# GTU-2-V1_0-20160324.net
KiCad netlist of a schematic drawn in Altium Designer
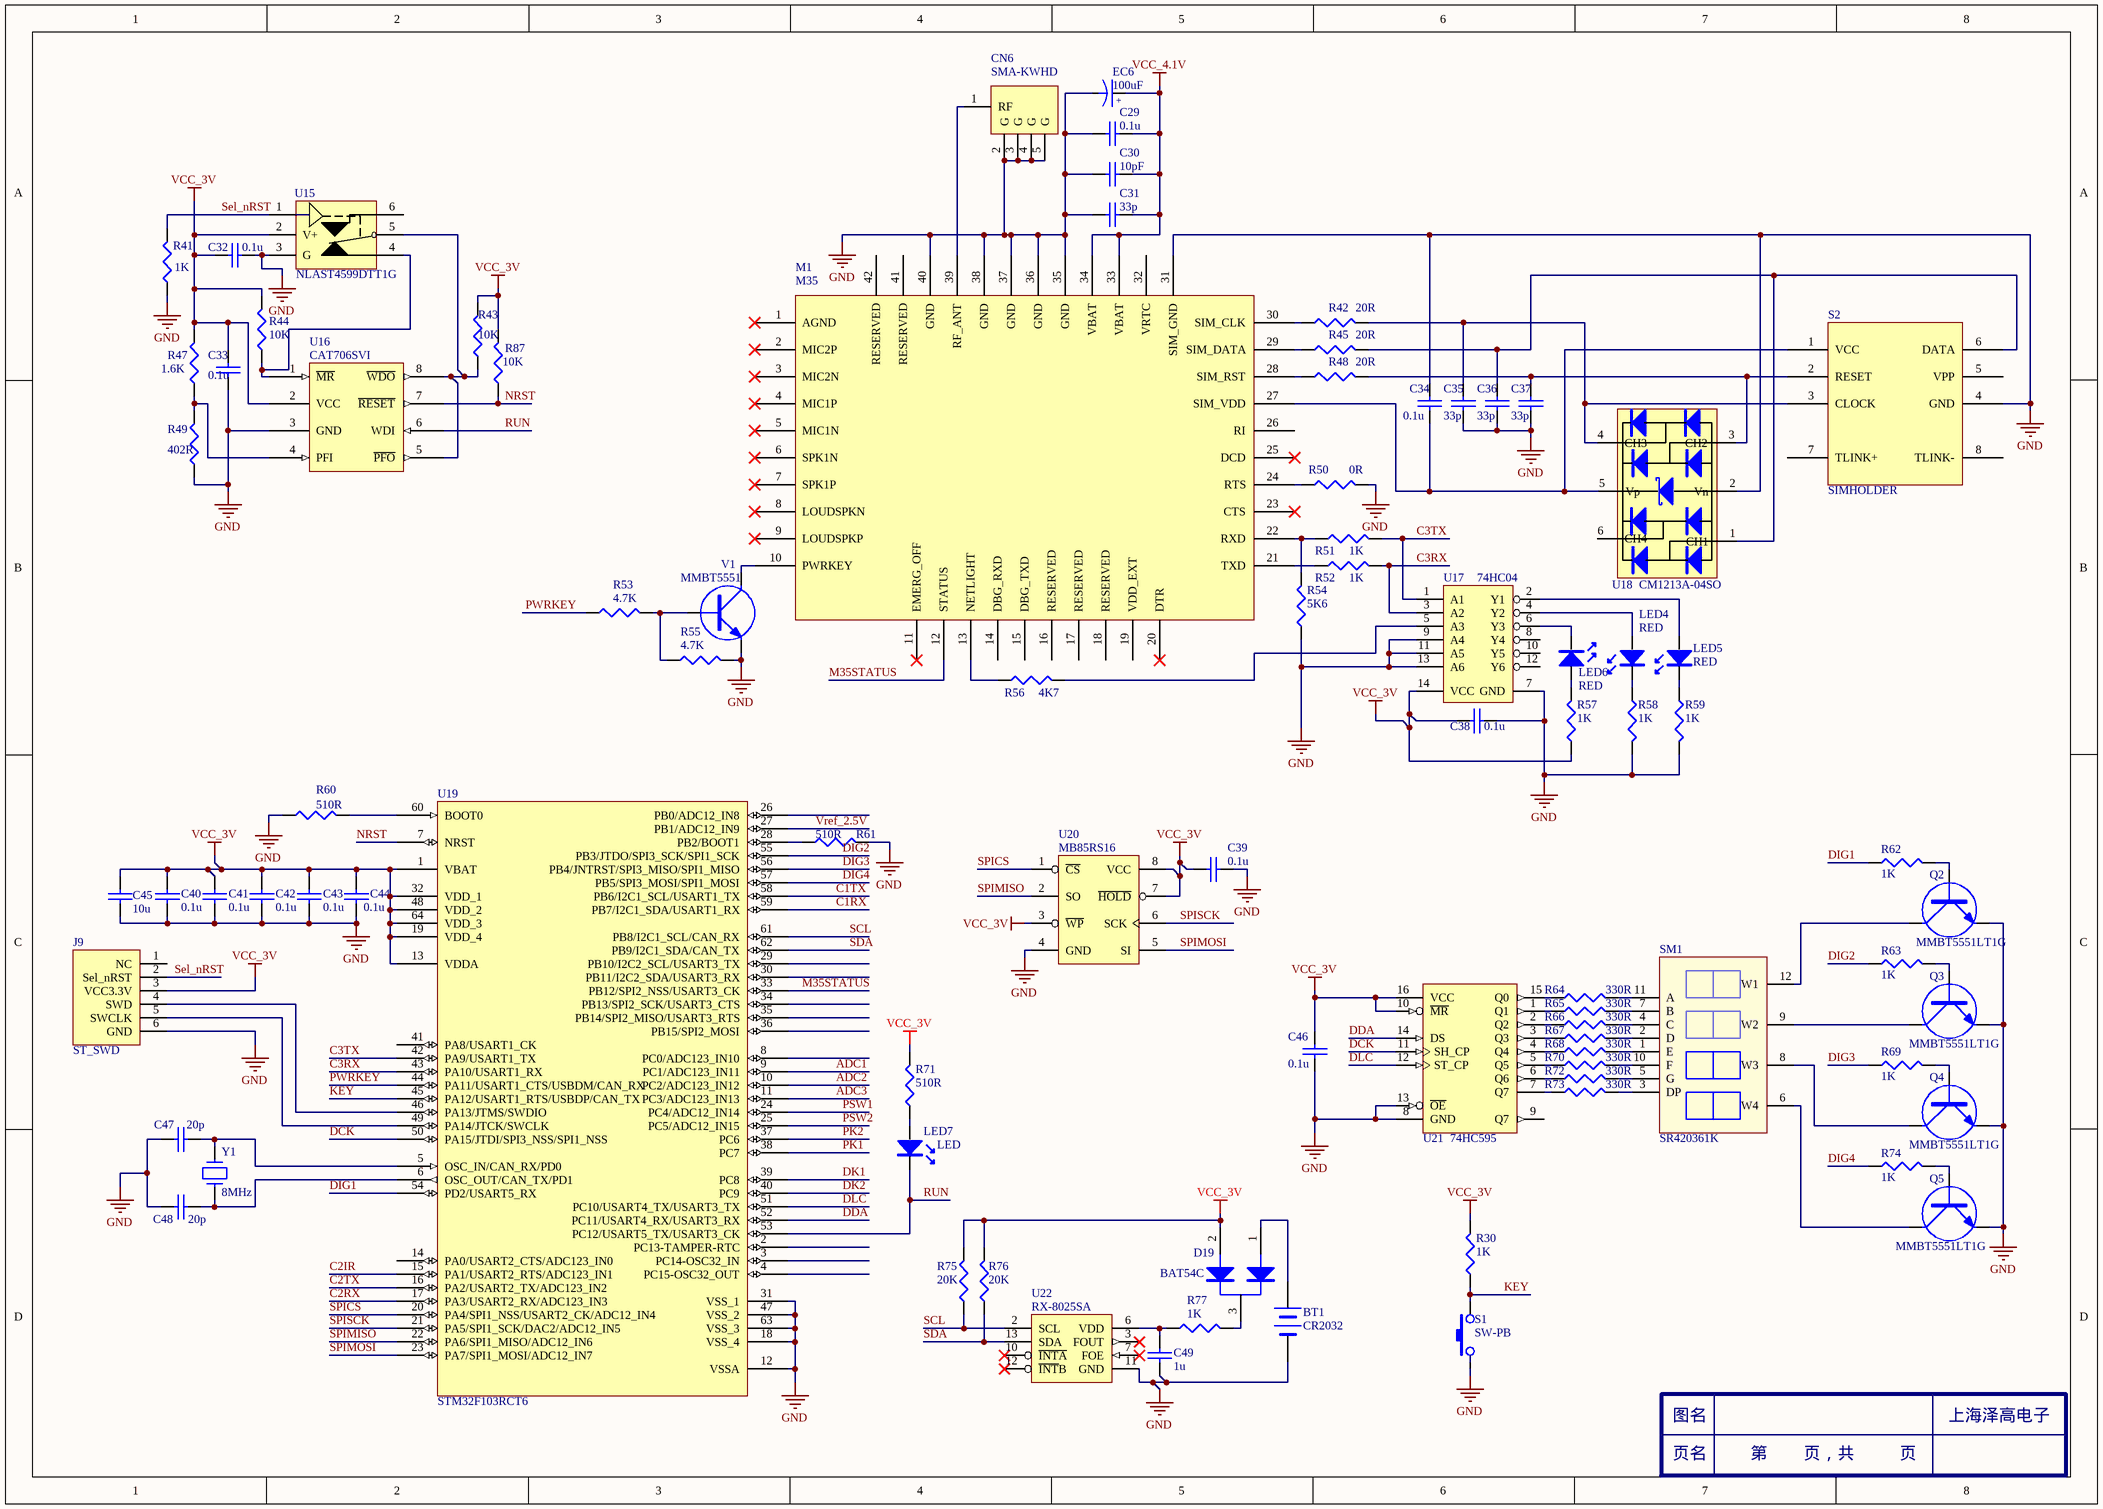
[diagram p0: GTU-2-V1.0-20160324.SCHDOC]

(export (version "E")
  (design (tool "Eeschema 10.0.6"))
  (components
    (comp (ref "4") (value "Component_1") (libsource (lib "*") (part "Component_1")))
    (comp (ref "BT1")
      (value "CR2032")
      (footprint "CR2032")
      (description "Battery")
      (libsource (lib "*") (part "BATTERY"))
    )
    (comp (ref "C29")
      (value "0.1u")
      (footprint "0805-C")
      (description "Capacitor")
      (libsource (lib "STSCH-2014-01-20    ") (part "CAP"))
    )
    (comp (ref "C30")
      (value "10pF")
      (footprint "0805-C")
      (description "Capacitor")
      (libsource (lib "STSCH-2014-01-20    ") (part "CAP"))
    )
    (comp (ref "C31")
      (value "33p")
      (footprint "0805-C")
      (description "Capacitor")
      (libsource (lib "STSCH-2014-01-20    ") (part "CAP"))
    )
    (comp (ref "C32")
      (value "0.1u")
      (footprint "0805-C")
      (description "Capacitor")
      (fields (field (name "MFG") "TDK"))
      (libsource (lib "SCHLIB-ZG-2015.12.11      ") (part "CAP"))
    )
    (comp (ref "C33")
      (value "0.1u")
      (footprint "0805-C")
      (description "Capacitor")
      (libsource (lib "STSCH-2011-12-16") (part "CAP"))
    )
    (comp (ref "C34")
      (value "0.1u")
      (footprint "0805-C")
      (description "Capacitor")
      (libsource (lib "STSCH-2014-01-20    ") (part "CAP"))
    )
    (comp (ref "C35")
      (value "33p")
      (footprint "0805-C")
      (description "Capacitor")
      (libsource (lib "STSCH-2014-01-20    ") (part "CAP"))
    )
    (comp (ref "C36")
      (value "33p")
      (footprint "0805-C")
      (description "Capacitor")
      (libsource (lib "STSCH-2014-01-20    ") (part "CAP"))
    )
    (comp (ref "C37")
      (value "33p")
      (footprint "0805-C")
      (description "Capacitor")
      (libsource (lib "STSCH-2014-01-20    ") (part "CAP"))
    )
    (comp (ref "C38")
      (value "0.1u")
      (footprint "0805-C")
      (description "Capacitor")
      (libsource (lib "STSCH-2013-02-22   ") (part "CAP"))
    )
    (comp (ref "C39")
      (value "0.1u")
      (footprint "0805-C")
      (description "Capacitor")
      (libsource (lib "STSCH-2013-02-22   ") (part "CAP"))
    )
    (comp (ref "C40")
      (value "0.1u")
      (footprint "0805-C")
      (description "Capacitor")
      (libsource (lib "*") (part "CAP"))
    )
    (comp (ref "C41")
      (value "0.1u")
      (footprint "0805-C")
      (description "Capacitor")
      (libsource (lib "*") (part "CAP"))
    )
    (comp (ref "C42")
      (value "0.1u")
      (footprint "0805-C")
      (description "Capacitor")
      (libsource (lib "*") (part "CAP"))
    )
    (comp (ref "C43")
      (value "0.1u")
      (footprint "0805-C")
      (description "Capacitor")
      (libsource (lib "*") (part "CAP"))
    )
    (comp (ref "C44")
      (value "0.1u")
      (footprint "0805-C")
      (description "Capacitor")
      (libsource (lib "*") (part "CAP"))
    )
    (comp (ref "C45")
      (value "10u")
      (footprint "0805-C")
      (description "Capacitor")
      (libsource (lib "*") (part "CAP"))
    )
    (comp (ref "C46")
      (value "0.1u")
      (footprint "0805-C")
      (description "Capacitor")
      (libsource (lib "STSCH-2013-02-22   ") (part "CAP"))
    )
    (comp (ref "C47")
      (value "20p")
      (footprint "0805-C")
      (description "Capacitor")
      (libsource (lib "*") (part "CAP"))
    )
    (comp (ref "C48")
      (value "20p")
      (footprint "0805-C")
      (description "Capacitor")
      (libsource (lib "*") (part "CAP"))
    )
    (comp (ref "C49")
      (value "1u")
      (footprint "0805-C")
      (description "Capacitor")
      (libsource (lib "") (part "CAP_1"))
    )
    (comp (ref "CN6")
      (value "SMA-KWHD")
      (footprint "SMA-KWHD")
      (description "RF插座")
      (libsource (lib "STSCH-2014-02-13    ") (part "SMA-KWHD"))
    )
    (comp (ref "D19") (value "BAT54C") (footprint "BAT54S/SOT-23") (libsource (lib "*") (part "BAT54C")))
    (comp (ref "EC6")
      (value "100uF")
      (footprint "7361-V")
      (libsource (lib "STSCH-2014-01-20    ") (part "CAP Tan"))
    )
    (comp (ref "J9")
      (value "ST_SWD")
      (footprint "SWD_DOWNLOAD")
      (description "STM32 SWD调试端口")
      (libsource (lib "SCHLIB-ZG-2015.12.11      ") (part "ST_SWD"))
    )
    (comp (ref "LED4")
      (value "RED")
      (footprint "0805-LED")
      (libsource (lib "STSCH-2012-11-26   ") (part "LED"))
    )
    (comp (ref "LED5")
      (value "RED")
      (footprint "0805-LED")
      (libsource (lib "STSCH-2012-11-26   ") (part "LED"))
    )
    (comp (ref "LED6")
      (value "RED")
      (footprint "0805-LED")
      (libsource (lib "STSCH-2012-11-26   ") (part "LED"))
    )
    (comp (ref "LED7") (value "LED") (footprint "0805-LED") (libsource (lib "STSCH-20110618") (part "LED")))
    (comp (ref "M1") (value "M35") (footprint "M35") (libsource (lib "STSCH-2014-01-20    ") (part "M35")))
    (comp (ref "Q2")
      (value "MMBT5551")
      (footprint "SOT-23")
      (description "NPN Transistor 160V 0.6A")
      (fields (field (name "MFG") "DIODES") (field (name "MFG2-PN") "MMBT5551LT1G"))
      (libsource (lib "SCHLIB-ZG-2016.01.18      ") (part "MMBT5551"))
    )
    (comp (ref "Q3")
      (value "MMBT5551")
      (footprint "SOT-23")
      (description "NPN Transistor 160V 0.6A")
      (fields (field (name "MFG") "DIODES") (field (name "MFG2-PN") "MMBT5551LT1G"))
      (libsource (lib "SCHLIB-ZG-2016.01.18      ") (part "MMBT5551"))
    )
    (comp (ref "Q4")
      (value "MMBT5551")
      (footprint "SOT-23")
      (description "NPN Transistor 160V 0.6A")
      (fields (field (name "MFG") "DIODES") (field (name "MFG2-PN") "MMBT5551LT1G"))
      (libsource (lib "SCHLIB-ZG-2016.01.18      ") (part "MMBT5551"))
    )
    (comp (ref "Q5")
      (value "MMBT5551")
      (footprint "SOT-23")
      (description "NPN Transistor 160V 0.6A")
      (fields (field (name "MFG") "DIODES") (field (name "MFG2-PN") "MMBT5551LT1G"))
      (libsource (lib "SCHLIB-ZG-2016.01.18      ") (part "MMBT5551"))
    )
    (comp (ref "R30") (value "1K") (footprint "0805-R") (libsource (lib "STSCH-2014-03-27    ") (part "RES")))
    (comp (ref "R41")
      (value "1K")
      (footprint "0805-R")
      (description "电阻")
      (fields (field (name "MFG") "YAGO") (field (name "Comment") "RES"))
      (libsource (lib "SCHLIB-ZG-2015.12.11      ") (part "RES"))
    )
    (comp (ref "R42")
      (value "20R")
      (footprint "0805-R")
      (libsource (lib "STSCH-2014-01-20    ") (part "RES"))
    )
    (comp (ref "R43") (value "10K") (footprint "0805-R") (libsource (lib "*") (part "RES")))
    (comp (ref "R44") (value "10K") (footprint "0805-R") (libsource (lib "*") (part "RES")))
    (comp (ref "R45")
      (value "20R")
      (footprint "0805-R")
      (libsource (lib "STSCH-2014-01-20    ") (part "RES"))
    )
    (comp (ref "R47")
      (value "1.6K")
      (footprint "0805-R")
      (description "电阻")
      (fields (field (name "MFG") "YAGO"))
      (libsource (lib "SCHLIB-ZG-2015.12.11      ") (part "RES"))
    )
    (comp (ref "R48")
      (value "20R")
      (footprint "0805-R")
      (libsource (lib "STSCH-2014-01-20    ") (part "RES"))
    )
    (comp (ref "R49")
      (value "402R")
      (footprint "0805-R")
      (description "电阻")
      (fields (field (name "MFG") "YAGO"))
      (libsource (lib "SCHLIB-ZG-2015.12.11      ") (part "RES"))
    )
    (comp (ref "R50") (value "0R") (footprint "0805-R") (libsource (lib "STSCH-2014-01-20    ") (part "RES")))
    (comp (ref "R51") (value "1K") (footprint "0805-R") (libsource (lib "STSCH-2014-01-20    ") (part "RES")))
    (comp (ref "R52") (value "1K") (footprint "0805-R") (libsource (lib "STSCH-2014-01-20    ") (part "RES")))
    (comp (ref "R53")
      (value "4.7K")
      (footprint "0805-R")
      (libsource (lib "STSCH-2014-01-20    ") (part "RES"))
    )
    (comp (ref "R54")
      (value "5K6")
      (footprint "0805-R")
      (libsource (lib "STSCH-2014-01-20    ") (part "RES"))
    )
    (comp (ref "R55")
      (value "4.7K")
      (footprint "0805-R")
      (libsource (lib "STSCH-2014-01-20    ") (part "RES"))
    )
    (comp (ref "R56")
      (value "4K7")
      (footprint "0805-R")
      (libsource (lib "STSCH-2014-02-12    ") (part "RES"))
    )
    (comp (ref "R57") (value "1K") (footprint "0805-R") (libsource (lib "STSCH-2012-11-26   ") (part "RES")))
    (comp (ref "R58") (value "1K") (footprint "0805-R") (libsource (lib "STSCH-2012-11-26   ") (part "RES")))
    (comp (ref "R59") (value "1K") (footprint "0805-R") (libsource (lib "STSCH-2012-11-26   ") (part "RES")))
    (comp (ref "R60") (value "510R") (footprint "0805-R") (libsource (lib "*") (part "RES")))
    (comp (ref "R61") (value "510R") (footprint "0805-R") (libsource (lib "*") (part "RES")))
    (comp (ref "R62")
      (value "1K")
      (footprint "0805-R")
      (description "电阻")
      (fields (field (name "MFG") "YAGO") (field (name "Comment") "RES"))
      (libsource (lib "SCHLIB-ZG-2016.01.18      ") (part "RES"))
    )
    (comp (ref "R63")
      (value "1K")
      (footprint "0805-R")
      (description "电阻")
      (fields (field (name "MFG") "YAGO") (field (name "Comment") "RES"))
      (libsource (lib "SCHLIB-ZG-2016.01.18      ") (part "RES"))
    )
    (comp (ref "R64") (value "330R") (footprint "0805-R") (libsource (lib "") (part "RES_1")))
    (comp (ref "R65") (value "330R") (footprint "0805-R") (libsource (lib "") (part "RES_1")))
    (comp (ref "R66") (value "330R") (footprint "0805-R") (libsource (lib "") (part "RES_1")))
    (comp (ref "R67") (value "330R") (footprint "0805-R") (libsource (lib "") (part "RES_1")))
    (comp (ref "R68") (value "330R") (footprint "0805-R") (libsource (lib "") (part "RES_1")))
    (comp (ref "R69")
      (value "1K")
      (footprint "0805-R")
      (description "电阻")
      (fields (field (name "MFG") "YAGO") (field (name "Comment") "RES"))
      (libsource (lib "SCHLIB-ZG-2016.01.18      ") (part "RES"))
    )
    (comp (ref "R70") (value "330R") (footprint "0805-R") (libsource (lib "") (part "RES_1")))
    (comp (ref "R71") (value "510R") (footprint "0805-R") (libsource (lib "STSCH-20110618") (part "RES")))
    (comp (ref "R72") (value "330R") (footprint "0805-R") (libsource (lib "") (part "RES_1")))
    (comp (ref "R73") (value "330R") (footprint "0805-R") (libsource (lib "") (part "RES_1")))
    (comp (ref "R74")
      (value "1K")
      (footprint "0805-R")
      (description "电阻")
      (fields (field (name "MFG") "YAGO") (field (name "Comment") "RES"))
      (libsource (lib "SCHLIB-ZG-2016.01.18      ") (part "RES"))
    )
    (comp (ref "R75") (value "20K") (footprint "0805-R") (libsource (lib "") (part "RES_1")))
    (comp (ref "R76") (value "20K") (footprint "0805-R") (libsource (lib "") (part "RES_1")))
    (comp (ref "R77") (value "1K") (footprint "0805-R") (libsource (lib "STSCH-2013-08-08    ") (part "RES")))
    (comp (ref "R87") (value "10K") (footprint "0805-R") (libsource (lib "*") (part "RES")))
    (comp (ref "S1")
      (value "SW-PB")
      (footprint "JMP")
      (description "轻触按钮")
      (libsource (lib "STSCH-2014-03-27    ") (part "SW-PB"))
    )
    (comp (ref "S2")
      (value "SIMHOLDER")
      (footprint "SIM-HOLDER")
      (libsource (lib "STSCH-2014-01-20    ") (part "SIMHOLDER"))
    )
    (comp (ref "SM1")
      (value "SR420361K")
      (footprint "SR420361")
      (description "共阴极0.28寸4位数码管品牌ARK")
      (libsource (lib "SCHLIB-ZG-2016.01.18      ") (part "SR420361"))
    )
    (comp (ref "U15")
      (value "NLAST4599DTT1G")
      (footprint "SOT-23-6")
      (libsource (lib "轨旁检测-20151210") (part "NLAST4599DTT1G"))
    )
    (comp (ref "U16") (value "CAT706SVI") (footprint "SO-8") (libsource (lib "*") (part "SP706T")))
    (comp (ref "U17")
      (value "74HC04")
      (footprint "SO-14")
      (libsource (lib "STSCH-2014-05-18     ") (part "74HC04"))
    )
    (comp (ref "U18")
      (value "CM1213A-04SO")
      (footprint "SOT-23-6")
      (libsource (lib "STSCH-2015.09.30  ") (part "CM1213A-04SO"))
    )
    (comp (ref "U19")
      (value "STM32F103RCT6")
      (footprint "LQFP-64")
      (libsource (lib "STSCH-2014-01-15") (part "STM32F103RCT6"))
    )
    (comp (ref "U20")
      (value "MB85RS16")
      (footprint "SO-8")
      (libsource (lib "STSCH-2013-02-22   ") (part "FM25256B"))
    )
    (comp (ref "U21")
      (value "74HC595")
      (footprint "SO-16")
      (description "8位移位寄存器")
      (fields (field (name "MFG") "NXP"))
      (libsource (lib "SCHLIB-ZG-2016.01.18      ") (part "74HC595"))
    )
    (comp (ref "U22") (value "RX-8025SA") (footprint "SO-14") (libsource (lib "*") (part "RX-8025SA")))
    (comp (ref "V1")
      (value "MMBT5551")
      (footprint "SOT-23")
      (description "贴片NPN")
      (libsource (lib "STSCH-2014-01-20    ") (part "MMBT5551"))
    )
    (comp (ref "Y1")
      (value "8MHz")
      (footprint "SM-49")
      (description "Crystal")
      (libsource (lib "*") (part "CRYSTAL"))
    )
  )
  (nets
    (net (code "1") (name "/ADC1") (class "Default")
      (node (ref "U19") (pin "9") (pinfunction "PC1/ADC123_IN11_9") (pintype "bidirectional"))
    )
    (net (code "2") (name "/ADC2") (class "Default")
      (node (ref "U19") (pin "10") (pinfunction "PC2/ADC123_IN12_10") (pintype "bidirectional"))
    )
    (net (code "3") (name "/ADC3") (class "Default")
      (node (ref "U19") (pin "11") (pinfunction "PC3/ADC123_IN13_11") (pintype "bidirectional"))
    )
    (net (code "4") (name "/C1RX") (class "Default")
      (node (ref "U19") (pin "59") (pinfunction "PB7/I2C1_SDA/USART1_RX_59") (pintype "bidirectional"))
    )
    (net (code "5") (name "/C1TX") (class "Default")
      (node (ref "U19") (pin "58") (pinfunction "PB6/I2C1_SCL/USART1_TX_58") (pintype "bidirectional"))
    )
    (net (code "6") (name "/C2IR") (class "Default")
      (node (ref "U19") (pin "15") (pinfunction "PA1/USART2_RTS/ADC123_IN1_15") (pintype "bidirectional"))
    )
    (net (code "7") (name "/C2RX") (class "Default")
      (node (ref "U19") (pin "17") (pinfunction "PA3/USART2_RX/ADC123_IN3_17") (pintype "bidirectional"))
    )
    (net (code "8") (name "/C2TX") (class "Default")
      (node (ref "U19") (pin "16") (pinfunction "PA2/USART2_TX/ADC123_IN2_16") (pintype "bidirectional"))
    )
    (net (code "9") (name "/C3RX") (class "Default")
      (node (ref "R52") (pin "2") (pinfunction "2_2") (pintype "passive"))
      (node (ref "U17") (pin "3") (pinfunction "A2_3") (pintype "passive"))
      (node (ref "U19") (pin "43") (pinfunction "PA10/USART1_RX_43") (pintype "bidirectional"))
    )
    (net (code "10") (name "/C3TX") (class "Default")
      (node (ref "R51") (pin "2") (pinfunction "2_2") (pintype "passive"))
      (node (ref "U17") (pin "1") (pinfunction "A1_1") (pintype "passive"))
      (node (ref "U19") (pin "42") (pinfunction "PA9/USART1_TX_42") (pintype "bidirectional"))
    )
    (net (code "11") (name "/DCK") (class "Default")
      (node (ref "U19") (pin "50") (pinfunction "PA15/JTDI/SPI3_NSS/SPI1_NSS_50") (pintype "bidirectional"))
      (node (ref "U21") (pin "11") (pinfunction "SH_CP_11") (pintype "input"))
    )
    (net (code "12") (name "/DDA") (class "Default")
      (node (ref "U19") (pin "52") (pinfunction "PC11/USART4_RX/USART3_RX_52") (pintype "bidirectional"))
      (node (ref "U21") (pin "14") (pinfunction "DS_14") (pintype "input"))
    )
    (net (code "13") (name "/DIG1") (class "Default")
      (node (ref "R62") (pin "1") (pinfunction "1_1") (pintype "passive"))
      (node (ref "U19") (pin "54") (pinfunction "PD2/USART5_RX_54") (pintype "bidirectional"))
    )
    (net (code "14") (name "/DIG2") (class "Default")
      (node (ref "R63") (pin "1") (pinfunction "1_1") (pintype "passive"))
      (node (ref "U19") (pin "55") (pinfunction "PB3/JTDO/SPI3_SCK/SPI1_SCK_55") (pintype "bidirectional"))
    )
    (net (code "15") (name "/DIG3") (class "Default")
      (node (ref "R69") (pin "1") (pinfunction "1_1") (pintype "passive"))
      (node (ref "U19") (pin "56") (pinfunction "PB4/JNTRST/SPI3_MISO/SPI1_MISO_56") (pintype "bidirectional"))
    )
    (net (code "16") (name "/DIG4") (class "Default")
      (node (ref "R74") (pin "1") (pinfunction "1_1") (pintype "passive"))
      (node (ref "U19") (pin "57") (pinfunction "PB5/SPI3_MOSI/SPI1_MOSI_57") (pintype "bidirectional"))
    )
    (net (code "17") (name "/DK1") (class "Default")
      (node (ref "U19") (pin "39") (pinfunction "PC8_39") (pintype "bidirectional"))
    )
    (net (code "18") (name "/DK2") (class "Default")
      (node (ref "U19") (pin "40") (pinfunction "PC9_40") (pintype "bidirectional"))
    )
    (net (code "19") (name "/DLC") (class "Default")
      (node (ref "U19") (pin "51") (pinfunction "PC10/USART4_TX/USART3_TX_51") (pintype "bidirectional"))
      (node (ref "U21") (pin "12") (pinfunction "ST_CP_12") (pintype "input"))
    )
    (net (code "20") (name "/KEY") (class "Default")
      (node (ref "R30") (pin "1") (pinfunction "1_1") (pintype "passive"))
      (node (ref "S1") (pin "2") (pinfunction "2_2") (pintype "passive"))
      (node (ref "U19") (pin "45") (pinfunction "PA12/USART1_RTS/USBDP/CAN_TX_45") (pintype "bidirectional"))
    )
    (net (code "21") (name "/M35STATUS") (class "Default")
      (node (ref "M1") (pin "12") (pinfunction "STATUS_12") (pintype "passive"))
      (node (ref "U19") (pin "33") (pinfunction "PB12/SPI2_NSS/USART3_CK_33") (pintype "bidirectional"))
    )
    (net (code "22") (name "/NRST") (class "Default")
      (node (ref "R87") (pin "1") (pinfunction "1_1") (pintype "passive"))
      (node (ref "U16") (pin "7") (pinfunction "~{RESET}_7") (pintype "output"))
      (node (ref "U19") (pin "7") (pinfunction "NRST_7") (pintype "bidirectional"))
    )
    (net (code "23") (name "/PK1") (class "Default")
      (node (ref "U19") (pin "38") (pinfunction "PC7_38") (pintype "bidirectional"))
    )
    (net (code "24") (name "/PK2") (class "Default")
      (node (ref "U19") (pin "37") (pinfunction "PC6_37") (pintype "bidirectional"))
    )
    (net (code "25") (name "/PSW1") (class "Default")
      (node (ref "U19") (pin "24") (pinfunction "PC4/ADC12_IN14_24") (pintype "bidirectional"))
    )
    (net (code "26") (name "/PSW2") (class "Default")
      (node (ref "U19") (pin "25") (pinfunction "PC5/ADC12_IN15_25") (pintype "bidirectional"))
    )
    (net (code "27") (name "/PWRKEY") (class "Default")
      (node (ref "R53") (pin "1") (pinfunction "1_1") (pintype "passive"))
      (node (ref "U19") (pin "44") (pinfunction "PA11/USART1_CTS/USBDM/CAN_RX_44") (pintype "bidirectional"))
    )
    (net (code "28") (name "/RUN") (class "Default")
      (node (ref "LED7") (pin "2") (pintype "passive"))
      (node (ref "U16") (pin "6") (pinfunction "WDI_6") (pintype "input"))
      (node (ref "U19") (pin "53") (pinfunction "PC12/USART5_TX/USART3_CK_53") (pintype "bidirectional"))
    )
    (net (code "29") (name "/SCL") (class "Default")
      (node (ref "R75") (pin "1") (pinfunction "1_1") (pintype "passive"))
      (node (ref "U19") (pin "61") (pinfunction "PB8/I2C1_SCL/CAN_RX_61") (pintype "bidirectional"))
      (node (ref "U22") (pin "2") (pinfunction "SCL_2") (pintype "open_collector"))
    )
    (net (code "30") (name "/SDA") (class "Default")
      (node (ref "R76") (pin "1") (pinfunction "1_1") (pintype "passive"))
      (node (ref "U19") (pin "62") (pinfunction "PB9/I2C1_SDA/CAN_TX_62") (pintype "bidirectional"))
      (node (ref "U22") (pin "13") (pinfunction "SDA_13") (pintype "passive"))
    )
    (net (code "31") (name "/SPICS") (class "Default")
      (node (ref "U19") (pin "20") (pinfunction "PA4/SPI1_NSS/USART2_CK/ADC12_IN4_20") (pintype "bidirectional"))
      (node (ref "U20") (pin "1") (pinfunction "~{CS}_1") (pintype "passive"))
    )
    (net (code "32") (name "/SPIMISO") (class "Default")
      (node (ref "U19") (pin "22") (pinfunction "PA6/SPI1_MISO/ADC12_IN6_22") (pintype "bidirectional"))
      (node (ref "U20") (pin "2") (pinfunction "SO_2") (pintype "passive"))
    )
    (net (code "33") (name "/SPIMOSI") (class "Default")
      (node (ref "U19") (pin "23") (pinfunction "PA7/SPI1_MOSI/ADC12_IN7_23") (pintype "bidirectional"))
      (node (ref "U20") (pin "5") (pinfunction "SI_5") (pintype "passive"))
    )
    (net (code "34") (name "/SPISCK") (class "Default")
      (node (ref "U19") (pin "21") (pinfunction "PA5/SPI1_SCK/DAC2/ADC12_IN5_21") (pintype "bidirectional"))
      (node (ref "U20") (pin "6") (pinfunction "SCK_6") (pintype "passive"))
    )
    (net (code "35") (name "/Sel_nRST") (class "Default")
      (node (ref "J9") (pin "2") (pinfunction "Sel_nRST_2") (pintype "passive"))
      (node (ref "R41") (pin "2") (pinfunction "2_2") (pintype "passive"))
      (node (ref "U15") (pin "1") (pinfunction "SELECT_1") (pintype "passive"))
    )
    (net (code "36") (name "/Vref_2.5V") (class "Default")
      (node (ref "U19") (pin "27") (pinfunction "PB1/ADC12_IN9_27") (pintype "bidirectional"))
    )
    (net (code "37") (name "GND") (class "Default")
      (node (ref "BT1") (pin "2") (pinfunction "-_2") (pintype "passive"))
      (node (ref "C29") (pin "2") (pinfunction "2_2") (pintype "passive"))
      (node (ref "C30") (pin "2") (pinfunction "2_2") (pintype "passive"))
      (node (ref "C31") (pin "2") (pinfunction "2_2") (pintype "passive"))
      (node (ref "C32") (pin "2") (pinfunction "2_2") (pintype "passive"))
      (node (ref "C33") (pin "2") (pinfunction "2_2") (pintype "passive"))
      (node (ref "C34") (pin "1") (pinfunction "1_1") (pintype "passive"))
      (node (ref "C35") (pin "2") (pinfunction "2_2") (pintype "passive"))
      (node (ref "C36") (pin "2") (pinfunction "2_2") (pintype "passive"))
      (node (ref "C37") (pin "2") (pinfunction "2_2") (pintype "passive"))
      (node (ref "C38") (pin "2") (pinfunction "2_2") (pintype "passive"))
      (node (ref "C39") (pin "2") (pinfunction "2_2") (pintype "passive"))
      (node (ref "C40") (pin "2") (pinfunction "2_2") (pintype "passive"))
      (node (ref "C41") (pin "2") (pinfunction "2_2") (pintype "passive"))
      (node (ref "C42") (pin "2") (pinfunction "2_2") (pintype "passive"))
      (node (ref "C43") (pin "2") (pinfunction "2_2") (pintype "passive"))
      (node (ref "C44") (pin "2") (pinfunction "2_2") (pintype "passive"))
      (node (ref "C45") (pin "2") (pinfunction "2_2") (pintype "passive"))
      (node (ref "C46") (pin "2") (pinfunction "2_2") (pintype "passive"))
      (node (ref "C47") (pin "2") (pinfunction "2_2") (pintype "passive"))
      (node (ref "C48") (pin "2") (pinfunction "2_2") (pintype "passive"))
      (node (ref "C49") (pin "2") (pinfunction "2_2") (pintype "passive"))
      (node (ref "CN6") (pin "2") (pinfunction "G_2") (pintype "passive"))
      (node (ref "CN6") (pin "3") (pinfunction "G_3") (pintype "passive"))
      (node (ref "CN6") (pin "4") (pinfunction "G_4") (pintype "passive"))
      (node (ref "CN6") (pin "5") (pinfunction "G_5") (pintype "passive"))
      (node (ref "EC6") (pin "2") (pinfunction "2_2") (pintype "passive"))
      (node (ref "J9") (pin "6") (pinfunction "GND_6") (pintype "passive"))
      (node (ref "M1") (pin "31") (pinfunction "SIM_GND_31") (pintype "passive"))
      (node (ref "M1") (pin "35") (pinfunction "GND_35") (pintype "passive"))
      (node (ref "M1") (pin "36") (pinfunction "GND_36") (pintype "passive"))
      (node (ref "M1") (pin "37") (pinfunction "GND_37") (pintype "passive"))
      (node (ref "M1") (pin "38") (pinfunction "GND_38") (pintype "passive"))
      (node (ref "M1") (pin "40") (pinfunction "GND_40") (pintype "passive"))
      (node (ref "Q2") (pin "2") (pinfunction "E_2") (pintype "passive"))
      (node (ref "Q3") (pin "2") (pinfunction "E_2") (pintype "passive"))
      (node (ref "Q4") (pin "2") (pinfunction "E_2") (pintype "passive"))
      (node (ref "Q5") (pin "2") (pinfunction "E_2") (pintype "passive"))
      (node (ref "R41") (pin "1") (pinfunction "1_1") (pintype "passive"))
      (node (ref "R49") (pin "1") (pinfunction "1_1") (pintype "passive"))
      (node (ref "R50") (pin "2") (pinfunction "2_2") (pintype "passive"))
      (node (ref "R54") (pin "1") (pinfunction "1_1") (pintype "passive"))
      (node (ref "R55") (pin "2") (pinfunction "2_2") (pintype "passive"))
      (node (ref "R58") (pin "2") (pinfunction "2_2") (pintype "passive"))
      (node (ref "R59") (pin "2") (pinfunction "2_2") (pintype "passive"))
      (node (ref "R60") (pin "1") (pinfunction "1_1") (pintype "passive"))
      (node (ref "R61") (pin "2") (pinfunction "2_2") (pintype "passive"))
      (node (ref "S1") (pin "1") (pinfunction "1_1") (pintype "passive"))
      (node (ref "S2") (pin "4") (pinfunction "GND_4") (pintype "passive"))
      (node (ref "U15") (pin "3") (pinfunction "G_3") (pintype "passive"))
      (node (ref "U16") (pin "3") (pinfunction "GND_3") (pintype "power_in"))
      (node (ref "U17") (pin "11") (pinfunction "A5_11") (pintype "passive"))
      (node (ref "U17") (pin "13") (pinfunction "A6_13") (pintype "passive"))
      (node (ref "U17") (pin "7") (pinfunction "GND_7") (pintype "passive"))
      (node (ref "U17") (pin "9") (pinfunction "A4_9") (pintype "passive"))
      (node (ref "U18") (pin "2") (pinfunction "Vn_2") (pintype "passive"))
      (node (ref "U19") (pin "12") (pinfunction "VSSA_12") (pintype "power_in"))
      (node (ref "U19") (pin "18") (pinfunction "VSS_4_18") (pintype "power_in"))
      (node (ref "U19") (pin "31") (pinfunction "VSS_1_31") (pintype "power_in"))
      (node (ref "U19") (pin "47") (pinfunction "VSS_2_47") (pintype "power_in"))
      (node (ref "U19") (pin "63") (pinfunction "VSS_3_63") (pintype "power_in"))
      (node (ref "U20") (pin "4") (pinfunction "GND_4") (pintype "passive"))
      (node (ref "U21") (pin "13") (pinfunction "~{OE}_13") (pintype "input"))
      (node (ref "U21") (pin "8") (pinfunction "GND_8") (pintype "power_in"))
      (node (ref "U22") (pin "11") (pinfunction "GND_11") (pintype "power_in"))
      (node (ref "V1") (pin "2") (pinfunction "E_2") (pintype "passive"))
    )
    (net (code "38") (name "Net-(BT1-+)") (class "Default")
      (node (ref "BT1") (pin "1") (pinfunction "+_1") (pintype "passive"))
      (node (ref "D19") (pin "1") (pintype "passive"))
    )
    (net (code "39") (name "Net-(CN6-RF)") (class "Default")
      (node (ref "CN6") (pin "1") (pinfunction "RF_1") (pintype "passive"))
      (node (ref "M1") (pin "39") (pinfunction "RF_ANT_39") (pintype "passive"))
    )
    (net (code "40") (name "Net-(D19-Pad3)") (class "Default")
      (node (ref "D19") (pin "3") (pintype "passive"))
      (node (ref "R77") (pin "2") (pinfunction "2_2") (pintype "passive"))
    )
    (net (code "41") (name "Net-(J9-SWCLK)") (class "Default")
      (node (ref "J9") (pin "5") (pinfunction "SWCLK_5") (pintype "passive"))
      (node (ref "U19") (pin "49") (pinfunction "PA14/JTCK/SWCLK_49") (pintype "bidirectional"))
    )
    (net (code "42") (name "Net-(J9-SWD)") (class "Default")
      (node (ref "J9") (pin "4") (pinfunction "SWD_4") (pintype "passive"))
      (node (ref "U19") (pin "46") (pinfunction "PA13/JTMS/SWDIO_46") (pintype "bidirectional"))
    )
    (net (code "43") (name "Net-(LED4-Pad2)") (class "Default")
      (node (ref "LED4") (pin "2") (pintype "passive"))
      (node (ref "R58") (pin "1") (pinfunction "1_1") (pintype "passive"))
    )
    (net (code "44") (name "Net-(LED5-Pad2)") (class "Default")
      (node (ref "LED5") (pin "2") (pintype "passive"))
      (node (ref "R59") (pin "1") (pinfunction "1_1") (pintype "passive"))
    )
    (net (code "45") (name "Net-(LED6-Pad1)") (class "Default")
      (node (ref "LED6") (pin "1") (pintype "passive"))
      (node (ref "R57") (pin "2") (pinfunction "2_2") (pintype "passive"))
    )
    (net (code "46") (name "Net-(LED7-Pad1)") (class "Default")
      (node (ref "LED7") (pin "1") (pintype "passive"))
      (node (ref "R71") (pin "1") (pinfunction "1_1") (pintype "passive"))
    )
    (net (code "47") (name "Net-(M1-NETLIGHT)") (class "Default")
      (node (ref "M1") (pin "13") (pinfunction "NETLIGHT_13") (pintype "passive"))
      (node (ref "R56") (pin "1") (pinfunction "1_1") (pintype "passive"))
    )
    (net (code "48") (name "Net-(M1-PWRKEY)") (class "Default")
      (node (ref "M1") (pin "10") (pinfunction "PWRKEY_10") (pintype "passive"))
      (node (ref "V1") (pin "3") (pinfunction "C_3") (pintype "passive"))
    )
    (net (code "49") (name "Net-(M1-RTS)") (class "Default")
      (node (ref "M1") (pin "24") (pinfunction "RTS_24") (pintype "passive"))
      (node (ref "R50") (pin "1") (pinfunction "1_1") (pintype "passive"))
    )
    (net (code "50") (name "Net-(M1-RXD)") (class "Default")
      (node (ref "M1") (pin "22") (pinfunction "RXD_22") (pintype "passive"))
      (node (ref "R51") (pin "1") (pinfunction "1_1") (pintype "passive"))
      (node (ref "R54") (pin "2") (pinfunction "2_2") (pintype "passive"))
    )
    (net (code "51") (name "Net-(M1-SIM_CLK)") (class "Default")
      (node (ref "M1") (pin "30") (pinfunction "SIM_CLK_30") (pintype "passive"))
      (node (ref "R42") (pin "1") (pinfunction "1_1") (pintype "passive"))
    )
    (net (code "52") (name "Net-(M1-SIM_DATA)") (class "Default")
      (node (ref "M1") (pin "29") (pinfunction "SIM_DATA_29") (pintype "passive"))
      (node (ref "R45") (pin "1") (pinfunction "1_1") (pintype "passive"))
    )
    (net (code "53") (name "Net-(M1-SIM_RST)") (class "Default")
      (node (ref "M1") (pin "28") (pinfunction "SIM_RST_28") (pintype "passive"))
      (node (ref "R48") (pin "1") (pinfunction "1_1") (pintype "passive"))
    )
    (net (code "54") (name "Net-(M1-SIM_VDD)") (class "Default")
      (node (ref "C34") (pin "2") (pinfunction "2_2") (pintype "passive"))
      (node (ref "M1") (pin "27") (pinfunction "SIM_VDD_27") (pintype "passive"))
      (node (ref "S2") (pin "1") (pinfunction "VCC_1") (pintype "passive"))
      (node (ref "U18") (pin "5") (pinfunction "Vp_5") (pintype "passive"))
    )
    (net (code "55") (name "Net-(M1-TXD)") (class "Default")
      (node (ref "M1") (pin "21") (pinfunction "TXD_21") (pintype "passive"))
      (node (ref "R52") (pin "1") (pinfunction "1_1") (pintype "passive"))
    )
    (net (code "56") (name "Net-(Q2-B)") (class "Default")
      (node (ref "Q2") (pin "1") (pinfunction "B_1") (pintype "passive"))
      (node (ref "R62") (pin "2") (pinfunction "2_2") (pintype "passive"))
    )
    (net (code "57") (name "Net-(Q2-C)") (class "Default")
      (node (ref "Q2") (pin "3") (pinfunction "C_3") (pintype "passive"))
      (node (ref "SM1") (pin "12") (pinfunction "W1_12") (pintype "passive"))
    )
    (net (code "58") (name "Net-(Q3-B)") (class "Default")
      (node (ref "Q3") (pin "1") (pinfunction "B_1") (pintype "passive"))
      (node (ref "R63") (pin "2") (pinfunction "2_2") (pintype "passive"))
    )
    (net (code "59") (name "Net-(Q3-C)") (class "Default")
      (node (ref "Q3") (pin "3") (pinfunction "C_3") (pintype "passive"))
      (node (ref "SM1") (pin "9") (pinfunction "W2_9") (pintype "passive"))
    )
    (net (code "60") (name "Net-(Q4-B)") (class "Default")
      (node (ref "Q4") (pin "1") (pinfunction "B_1") (pintype "passive"))
      (node (ref "R69") (pin "2") (pinfunction "2_2") (pintype "passive"))
    )
    (net (code "61") (name "Net-(Q4-C)") (class "Default")
      (node (ref "Q4") (pin "3") (pinfunction "C_3") (pintype "passive"))
      (node (ref "SM1") (pin "8") (pinfunction "W3_8") (pintype "passive"))
    )
    (net (code "62") (name "Net-(Q5-B)") (class "Default")
      (node (ref "Q5") (pin "1") (pinfunction "B_1") (pintype "passive"))
      (node (ref "R74") (pin "2") (pinfunction "2_2") (pintype "passive"))
    )
    (net (code "63") (name "Net-(Q5-C)") (class "Default")
      (node (ref "Q5") (pin "3") (pinfunction "C_3") (pintype "passive"))
      (node (ref "SM1") (pin "6") (pinfunction "W4_6") (pintype "passive"))
    )
    (net (code "64") (name "Net-(R73-Pad1)") (class "Default")
      (node (ref "R73") (pin "1") (pinfunction "1_1") (pintype "passive"))
      (node (ref "U21") (pin "7") (pinfunction "Q7_7") (pintype "tri_state"))
    )
    (net (code "65") (name "Net-(S2-CLOCK)") (class "Default")
      (node (ref "C35") (pin "1") (pinfunction "1_1") (pintype "passive"))
      (node (ref "R42") (pin "2") (pinfunction "2_2") (pintype "passive"))
      (node (ref "S2") (pin "3") (pinfunction "CLOCK_3") (pintype "passive"))
      (node (ref "U18") (pin "4") (pinfunction "CH3_4") (pintype "passive"))
    )
    (net (code "66") (name "Net-(S2-DATA)") (class "Default")
      (node (ref "C36") (pin "1") (pinfunction "1_1") (pintype "passive"))
      (node (ref "R45") (pin "2") (pinfunction "2_2") (pintype "passive"))
      (node (ref "S2") (pin "6") (pinfunction "DATA_6") (pintype "passive"))
      (node (ref "U18") (pin "1") (pinfunction "CH1_1") (pintype "passive"))
    )
    (net (code "67") (name "Net-(S2-RESET)") (class "Default")
      (node (ref "C37") (pin "1") (pinfunction "1_1") (pintype "passive"))
      (node (ref "R48") (pin "2") (pinfunction "2_2") (pintype "passive"))
      (node (ref "S2") (pin "2") (pinfunction "RESET_2") (pintype "passive"))
      (node (ref "U18") (pin "3") (pinfunction "CH2_3") (pintype "passive"))
    )
    (net (code "68") (name "Net-(SM1-A)") (class "Default")
      (node (ref "R64") (pin "2") (pinfunction "2_2") (pintype "passive"))
      (node (ref "SM1") (pin "11") (pinfunction "A_11") (pintype "passive"))
    )
    (net (code "69") (name "Net-(SM1-B)") (class "Default")
      (node (ref "R65") (pin "2") (pinfunction "2_2") (pintype "passive"))
      (node (ref "SM1") (pin "7") (pinfunction "B_7") (pintype "passive"))
    )
    (net (code "70") (name "Net-(SM1-C)") (class "Default")
      (node (ref "R66") (pin "2") (pinfunction "2_2") (pintype "passive"))
      (node (ref "SM1") (pin "4") (pinfunction "C_4") (pintype "passive"))
    )
    (net (code "71") (name "Net-(SM1-D)") (class "Default")
      (node (ref "R67") (pin "2") (pinfunction "2_2") (pintype "passive"))
      (node (ref "SM1") (pin "2") (pinfunction "D_2") (pintype "passive"))
    )
    (net (code "72") (name "Net-(SM1-DP)") (class "Default")
      (node (ref "R73") (pin "2") (pinfunction "2_2") (pintype "passive"))
      (node (ref "SM1") (pin "3") (pinfunction "DP_3") (pintype "passive"))
    )
    (net (code "73") (name "Net-(SM1-E)") (class "Default")
      (node (ref "R68") (pin "2") (pinfunction "2_2") (pintype "passive"))
      (node (ref "SM1") (pin "1") (pinfunction "E_1") (pintype "passive"))
    )
    (net (code "74") (name "Net-(SM1-F)") (class "Default")
      (node (ref "R70") (pin "2") (pinfunction "2_2") (pintype "passive"))
      (node (ref "SM1") (pin "10") (pinfunction "F_10") (pintype "passive"))
    )
    (net (code "75") (name "Net-(SM1-G)") (class "Default")
      (node (ref "R72") (pin "2") (pinfunction "2_2") (pintype "passive"))
      (node (ref "SM1") (pin "5") (pinfunction "G_5") (pintype "passive"))
    )
    (net (code "76") (name "Net-(U15-CON)") (class "Default")
      (node (ref "R43") (pin "1") (pinfunction "1_1") (pintype "passive"))
      (node (ref "U15") (pin "5") (pinfunction "CON_5") (pintype "passive"))
      (node (ref "U16") (pin "5") (pinfunction "~{PFO}_5") (pintype "output"))
      (node (ref "U16") (pin "8") (pinfunction "~{WDO}_8") (pintype "output"))
    )
    (net (code "77") (name "Net-(U15-NC)") (class "Default")
      (node (ref "R44") (pin "1") (pinfunction "1_1") (pintype "passive"))
      (node (ref "U15") (pin "4") (pinfunction "NC_4") (pintype "passive"))
      (node (ref "U16") (pin "1") (pinfunction "~{MR}_1") (pintype "input"))
    )
    (net (code "78") (name "Net-(U16-PFI)") (class "Default")
      (node (ref "R47") (pin "1") (pinfunction "1_1") (pintype "passive"))
      (node (ref "R49") (pin "2") (pinfunction "2_2") (pintype "passive"))
      (node (ref "U16") (pin "4") (pinfunction "PFI_4") (pintype "input"))
    )
    (net (code "79") (name "Net-(U17-A3)") (class "Default")
      (node (ref "R56") (pin "2") (pinfunction "2_2") (pintype "passive"))
      (node (ref "U17") (pin "5") (pinfunction "A3_5") (pintype "passive"))
    )
    (net (code "80") (name "Net-(U17-Y1)") (class "Default")
      (node (ref "LED5") (pin "1") (pintype "passive"))
      (node (ref "U17") (pin "2") (pinfunction "Y1_2") (pintype "passive"))
    )
    (net (code "81") (name "Net-(U17-Y2)") (class "Default")
      (node (ref "LED4") (pin "1") (pintype "passive"))
      (node (ref "U17") (pin "4") (pinfunction "Y2_4") (pintype "passive"))
    )
    (net (code "82") (name "Net-(U17-Y3)") (class "Default")
      (node (ref "LED6") (pin "2") (pintype "passive"))
      (node (ref "U17") (pin "6") (pinfunction "Y3_6") (pintype "passive"))
    )
    (net (code "83") (name "Net-(U19-BOOT0)") (class "Default")
      (node (ref "R60") (pin "2") (pinfunction "2_2") (pintype "passive"))
      (node (ref "U19") (pin "60") (pinfunction "BOOT0_60") (pintype "input"))
    )
    (net (code "84") (name "Net-(U19-OSC_IN{slash}CAN_RX{slash}PD0)") (class "Default")
      (node (ref "C47") (pin "1") (pinfunction "1_1") (pintype "passive"))
      (node (ref "U19") (pin "5") (pinfunction "OSC_IN/CAN_RX/PD0_5") (pintype "input"))
      (node (ref "Y1") (pin "2") (pinfunction "2_2") (pintype "passive"))
    )
    (net (code "85") (name "Net-(U19-OSC_OUT{slash}CAN_TX{slash}PD1)") (class "Default")
      (node (ref "C48") (pin "1") (pinfunction "1_1") (pintype "passive"))
      (node (ref "U19") (pin "6") (pinfunction "OSC_OUT/CAN_TX/PD1_6") (pintype "output"))
      (node (ref "Y1") (pin "1") (pinfunction "1_1") (pintype "passive"))
    )
    (net (code "86") (name "Net-(U19-PB2{slash}BOOT1)") (class "Default")
      (node (ref "R61") (pin "1") (pinfunction "1_1") (pintype "passive"))
      (node (ref "U19") (pin "28") (pinfunction "PB2/BOOT1_28") (pintype "bidirectional"))
    )
    (net (code "87") (name "Net-(U21-Q0)") (class "Default")
      (node (ref "R64") (pin "1") (pinfunction "1_1") (pintype "passive"))
      (node (ref "U21") (pin "15") (pinfunction "Q0_15") (pintype "output"))
    )
    (net (code "88") (name "Net-(U21-Q1)") (class "Default")
      (node (ref "R65") (pin "1") (pinfunction "1_1") (pintype "passive"))
      (node (ref "U21") (pin "1") (pinfunction "Q1_1") (pintype "output"))
    )
    (net (code "89") (name "Net-(U21-Q2)") (class "Default")
      (node (ref "R66") (pin "1") (pinfunction "1_1") (pintype "passive"))
      (node (ref "U21") (pin "2") (pinfunction "Q2_2") (pintype "output"))
    )
    (net (code "90") (name "Net-(U21-Q3)") (class "Default")
      (node (ref "R67") (pin "1") (pinfunction "1_1") (pintype "passive"))
      (node (ref "U21") (pin "3") (pinfunction "Q3_3") (pintype "output"))
    )
    (net (code "91") (name "Net-(U21-Q4)") (class "Default")
      (node (ref "R68") (pin "1") (pinfunction "1_1") (pintype "passive"))
      (node (ref "U21") (pin "4") (pinfunction "Q4_4") (pintype "output"))
    )
    (net (code "92") (name "Net-(U21-Q5)") (class "Default")
      (node (ref "R70") (pin "1") (pinfunction "1_1") (pintype "passive"))
      (node (ref "U21") (pin "5") (pinfunction "Q5_5") (pintype "output"))
    )
    (net (code "93") (name "Net-(U21-Q6)") (class "Default")
      (node (ref "R72") (pin "1") (pinfunction "1_1") (pintype "passive"))
      (node (ref "U21") (pin "6") (pinfunction "Q6_6") (pintype "output"))
    )
    (net (code "94") (name "Net-(U22-VDD)") (class "Default")
      (node (ref "C49") (pin "1") (pinfunction "1_1") (pintype "passive"))
      (node (ref "R77") (pin "1") (pinfunction "1_1") (pintype "passive"))
      (node (ref "U22") (pin "6") (pinfunction "VDD_6") (pintype "power_in"))
    )
    (net (code "95") (name "Net-(V1-B)") (class "Default")
      (node (ref "R53") (pin "2") (pinfunction "2_2") (pintype "passive"))
      (node (ref "R55") (pin "1") (pinfunction "1_1") (pintype "passive"))
      (node (ref "V1") (pin "1") (pinfunction "B_1") (pintype "passive"))
    )
    (net (code "96") (name "VCC_3V") (class "Default")
      (node (ref "C32") (pin "1") (pinfunction "1_1") (pintype "passive"))
      (node (ref "C33") (pin "1") (pinfunction "1_1") (pintype "passive"))
      (node (ref "C38") (pin "1") (pinfunction "1_1") (pintype "passive"))
      (node (ref "C39") (pin "1") (pinfunction "1_1") (pintype "passive"))
      (node (ref "C40") (pin "1") (pinfunction "1_1") (pintype "passive"))
      (node (ref "C41") (pin "1") (pinfunction "1_1") (pintype "passive"))
      (node (ref "C42") (pin "1") (pinfunction "1_1") (pintype "passive"))
      (node (ref "C43") (pin "1") (pinfunction "1_1") (pintype "passive"))
      (node (ref "C44") (pin "1") (pinfunction "1_1") (pintype "passive"))
      (node (ref "C45") (pin "1") (pinfunction "1_1") (pintype "passive"))
      (node (ref "C46") (pin "1") (pinfunction "1_1") (pintype "passive"))
      (node (ref "D19") (pin "2") (pintype "passive"))
      (node (ref "J9") (pin "3") (pinfunction "VCC3.3V_3") (pintype "passive"))
      (node (ref "R30") (pin "2") (pinfunction "2_2") (pintype "passive"))
      (node (ref "R43") (pin "2") (pinfunction "2_2") (pintype "passive"))
      (node (ref "R44") (pin "2") (pinfunction "2_2") (pintype "passive"))
      (node (ref "R47") (pin "2") (pinfunction "2_2") (pintype "passive"))
      (node (ref "R57") (pin "1") (pinfunction "1_1") (pintype "passive"))
      (node (ref "R71") (pin "2") (pinfunction "2_2") (pintype "passive"))
      (node (ref "R75") (pin "2") (pinfunction "2_2") (pintype "passive"))
      (node (ref "R76") (pin "2") (pinfunction "2_2") (pintype "passive"))
      (node (ref "R87") (pin "2") (pinfunction "2_2") (pintype "passive"))
      (node (ref "U15") (pin "2") (pinfunction "V+_2") (pintype "passive"))
      (node (ref "U16") (pin "2") (pinfunction "VCC_2") (pintype "power_in"))
      (node (ref "U17") (pin "14") (pinfunction "VCC_14") (pintype "passive"))
      (node (ref "U19") (pin "1") (pinfunction "VBAT_1") (pintype "power_in"))
      (node (ref "U19") (pin "13") (pinfunction "VDDA_13") (pintype "power_in"))
      (node (ref "U19") (pin "19") (pinfunction "VDD_4_19") (pintype "power_in"))
      (node (ref "U19") (pin "32") (pinfunction "VDD_1_32") (pintype "power_in"))
      (node (ref "U19") (pin "48") (pinfunction "VDD_2_48") (pintype "power_in"))
      (node (ref "U19") (pin "64") (pinfunction "VDD_3_64") (pintype "power_in"))
      (node (ref "U20") (pin "3") (pinfunction "~{WP}_3") (pintype "passive"))
      (node (ref "U20") (pin "7") (pinfunction "~{HOLD}_7") (pintype "passive"))
      (node (ref "U20") (pin "8") (pinfunction "VCC_8") (pintype "passive"))
      (node (ref "U21") (pin "10") (pinfunction "~{MR}_10") (pintype "input"))
      (node (ref "U21") (pin "16") (pinfunction "VCC_16") (pintype "power_in"))
    )
    (net (code "97") (name "VCC_4.1V") (class "Default")
      (node (ref "C29") (pin "1") (pinfunction "1_1") (pintype "passive"))
      (node (ref "C30") (pin "1") (pinfunction "1_1") (pintype "passive"))
      (node (ref "C31") (pin "1") (pinfunction "1_1") (pintype "passive"))
      (node (ref "EC6") (pin "1") (pinfunction "1_1") (pintype "passive"))
      (node (ref "M1") (pin "33") (pinfunction "VBAT_33") (pintype "passive"))
      (node (ref "M1") (pin "34") (pinfunction "VBAT_34") (pintype "passive"))
    )
    (net (code "98") (name "unconnected-(J9-NC-Pad1)") (class "Default")
      (node (ref "J9") (pin "1") (pinfunction "NC_1") (pintype "passive"))
    )
    (net (code "99") (name "unconnected-(M1-AGND-Pad1)") (class "Default")
      (node (ref "M1") (pin "1") (pinfunction "AGND_1") (pintype "passive+no_connect"))
    )
    (net (code "100") (name "unconnected-(M1-CTS-Pad23)") (class "Default")
      (node (ref "M1") (pin "23") (pinfunction "CTS_23") (pintype "passive+no_connect"))
    )
    (net (code "101") (name "unconnected-(M1-DBG_RXD-Pad14)") (class "Default")
      (node (ref "M1") (pin "14") (pinfunction "DBG_RXD_14") (pintype "passive"))
    )
    (net (code "102") (name "unconnected-(M1-DBG_TXD-Pad15)") (class "Default")
      (node (ref "M1") (pin "15") (pinfunction "DBG_TXD_15") (pintype "passive"))
    )
    (net (code "103") (name "unconnected-(M1-DCD-Pad25)") (class "Default")
      (node (ref "M1") (pin "25") (pinfunction "DCD_25") (pintype "passive+no_connect"))
    )
    (net (code "104") (name "unconnected-(M1-DTR-Pad20)") (class "Default")
      (node (ref "M1") (pin "20") (pinfunction "DTR_20") (pintype "passive+no_connect"))
    )
    (net (code "105") (name "unconnected-(M1-EMERG_OFF-Pad11)") (class "Default")
      (node (ref "M1") (pin "11") (pinfunction "EMERG_OFF_11") (pintype "passive+no_connect"))
    )
    (net (code "106") (name "unconnected-(M1-LOUDSPKN-Pad8)") (class "Default")
      (node (ref "M1") (pin "8") (pinfunction "LOUDSPKN_8") (pintype "passive+no_connect"))
    )
    (net (code "107") (name "unconnected-(M1-LOUDSPKP-Pad9)") (class "Default")
      (node (ref "M1") (pin "9") (pinfunction "LOUDSPKP_9") (pintype "passive+no_connect"))
    )
    (net (code "108") (name "unconnected-(M1-MIC1N-Pad5)") (class "Default")
      (node (ref "M1") (pin "5") (pinfunction "MIC1N_5") (pintype "passive+no_connect"))
    )
    (net (code "109") (name "unconnected-(M1-MIC1P-Pad4)") (class "Default")
      (node (ref "M1") (pin "4") (pinfunction "MIC1P_4") (pintype "passive+no_connect"))
    )
    (net (code "110") (name "unconnected-(M1-MIC2N-Pad3)") (class "Default")
      (node (ref "M1") (pin "3") (pinfunction "MIC2N_3") (pintype "passive+no_connect"))
    )
    (net (code "111") (name "unconnected-(M1-MIC2P-Pad2)") (class "Default")
      (node (ref "M1") (pin "2") (pinfunction "MIC2P_2") (pintype "passive+no_connect"))
    )
    (net (code "112") (name "unconnected-(M1-RESERVED-Pad16)") (class "Default")
      (node (ref "M1") (pin "16") (pinfunction "RESERVED_16") (pintype "passive"))
    )
    (net (code "113") (name "unconnected-(M1-RESERVED-Pad17)") (class "Default")
      (node (ref "M1") (pin "17") (pinfunction "RESERVED_17") (pintype "passive"))
    )
    (net (code "114") (name "unconnected-(M1-RESERVED-Pad18)") (class "Default")
      (node (ref "M1") (pin "18") (pinfunction "RESERVED_18") (pintype "passive"))
    )
    (net (code "115") (name "unconnected-(M1-RESERVED-Pad41)") (class "Default")
      (node (ref "M1") (pin "41") (pinfunction "RESERVED_41") (pintype "passive"))
    )
    (net (code "116") (name "unconnected-(M1-RESERVED-Pad42)") (class "Default")
      (node (ref "M1") (pin "42") (pinfunction "RESERVED_42") (pintype "passive"))
    )
    (net (code "117") (name "unconnected-(M1-RI-Pad26)") (class "Default")
      (node (ref "M1") (pin "26") (pinfunction "RI_26") (pintype "passive"))
    )
    (net (code "118") (name "unconnected-(M1-SPK1N-Pad6)") (class "Default")
      (node (ref "M1") (pin "6") (pinfunction "SPK1N_6") (pintype "passive+no_connect"))
    )
    (net (code "119") (name "unconnected-(M1-SPK1P-Pad7)") (class "Default")
      (node (ref "M1") (pin "7") (pinfunction "SPK1P_7") (pintype "passive+no_connect"))
    )
    (net (code "120") (name "unconnected-(M1-VDD_EXT-Pad19)") (class "Default")
      (node (ref "M1") (pin "19") (pinfunction "VDD_EXT_19") (pintype "passive"))
    )
    (net (code "121") (name "unconnected-(M1-VRTC-Pad32)") (class "Default")
      (node (ref "M1") (pin "32") (pinfunction "VRTC_32") (pintype "passive"))
    )
    (net (code "122") (name "unconnected-(S2-TLINK+-Pad7)") (class "Default")
      (node (ref "S2") (pin "7") (pinfunction "TLINK+_7") (pintype "passive"))
    )
    (net (code "123") (name "unconnected-(S2-TLINK--Pad8)") (class "Default")
      (node (ref "S2") (pin "8") (pinfunction "TLINK-_8") (pintype "passive"))
    )
    (net (code "124") (name "unconnected-(S2-VPP-Pad5)") (class "Default")
      (node (ref "S2") (pin "5") (pinfunction "VPP_5") (pintype "passive"))
    )
    (net (code "125") (name "unconnected-(U15-NO-Pad6)") (class "Default")
      (node (ref "U15") (pin "6") (pinfunction "NO_6") (pintype "passive"))
    )
    (net (code "126") (name "unconnected-(U17-Y4-Pad8)") (class "Default")
      (node (ref "U17") (pin "8") (pinfunction "Y4_8") (pintype "passive"))
    )
    (net (code "127") (name "unconnected-(U17-Y5-Pad10)") (class "Default")
      (node (ref "U17") (pin "10") (pinfunction "Y5_10") (pintype "passive"))
    )
    (net (code "128") (name "unconnected-(U17-Y6-Pad12)") (class "Default")
      (node (ref "U17") (pin "12") (pinfunction "Y6_12") (pintype "passive"))
    )
    (net (code "129") (name "unconnected-(U18-CH4-Pad6)") (class "Default")
      (node (ref "U18") (pin "6") (pinfunction "CH4_6") (pintype "passive"))
    )
    (net (code "130") (name "unconnected-(U19-PA0{slash}USART2_CTS{slash}ADC123_IN0-Pad14)") (class "Default")
      (node (ref "U19") (pin "14") (pinfunction "PA0/USART2_CTS/ADC123_IN0_14") (pintype "bidirectional"))
    )
    (net (code "131") (name "unconnected-(U19-PA8{slash}USART1_CK-Pad41)") (class "Default")
      (node (ref "U19") (pin "41") (pinfunction "PA8/USART1_CK_41") (pintype "bidirectional"))
    )
    (net (code "132") (name "unconnected-(U19-PB0{slash}ADC12_IN8-Pad26)") (class "Default")
      (node (ref "U19") (pin "26") (pinfunction "PB0/ADC12_IN8_26") (pintype "bidirectional"))
    )
    (net (code "133") (name "unconnected-(U19-PB10{slash}I2C2_SCL{slash}USART3_TX-Pad29)") (class "Default")
      (node (ref "U19") (pin "29") (pinfunction "PB10/I2C2_SCL/USART3_TX_29") (pintype "bidirectional"))
    )
    (net (code "134") (name "unconnected-(U19-PB11{slash}I2C2_SDA{slash}USART3_RX-Pad30)") (class "Default")
      (node (ref "U19") (pin "30") (pinfunction "PB11/I2C2_SDA/USART3_RX_30") (pintype "bidirectional"))
    )
    (net (code "135") (name "unconnected-(U19-PB13{slash}SPI2_SCK{slash}USART3_CTS-Pad34)") (class "Default")
      (node (ref "U19") (pin "34") (pinfunction "PB13/SPI2_SCK/USART3_CTS_34") (pintype "bidirectional"))
    )
    (net (code "136") (name "unconnected-(U19-PB14{slash}SPI2_MISO{slash}USART3_RTS-Pad35)") (class "Default")
      (node (ref "U19") (pin "35") (pinfunction "PB14/SPI2_MISO/USART3_RTS_35") (pintype "bidirectional"))
    )
    (net (code "137") (name "unconnected-(U19-PB15{slash}SPI2_MOSI-Pad36)") (class "Default")
      (node (ref "U19") (pin "36") (pinfunction "PB15/SPI2_MOSI_36") (pintype "bidirectional"))
    )
    (net (code "138") (name "unconnected-(U19-PC0{slash}ADC123_IN10-Pad8)") (class "Default")
      (node (ref "U19") (pin "8") (pinfunction "PC0/ADC123_IN10_8") (pintype "bidirectional"))
    )
    (net (code "139") (name "unconnected-(U19-PC13-TAMPER-RTC-Pad2)") (class "Default")
      (node (ref "U19") (pin "2") (pinfunction "PC13-TAMPER-RTC_2") (pintype "bidirectional"))
    )
    (net (code "140") (name "unconnected-(U19-PC14-OSC32_IN-Pad3)") (class "Default")
      (node (ref "U19") (pin "3") (pinfunction "PC14-OSC32_IN_3") (pintype "bidirectional"))
    )
    (net (code "141") (name "unconnected-(U19-PC15-OSC32_OUT-Pad4)") (class "Default")
      (node (ref "U19") (pin "4") (pinfunction "PC15-OSC32_OUT_4") (pintype "bidirectional"))
    )
    (net (code "142") (name "unconnected-(U21-Q7-Pad9)") (class "Default")
      (node (ref "U21") (pin "9") (pinfunction "Q7_9") (pintype "output"))
    )
    (net (code "143") (name "unconnected-(U22-FOE-Pad7)") (class "Default")
      (node (ref "U22") (pin "7") (pinfunction "FOE_7") (pintype "input+no_connect"))
    )
    (net (code "144") (name "unconnected-(U22-FOUT-Pad3)") (class "Default")
      (node (ref "U22") (pin "3") (pinfunction "FOUT_3") (pintype "output+no_connect"))
    )
    (net (code "145") (name "unconnected-(U22-~{INTA}-Pad10)") (class "Default")
      (node (ref "U22") (pin "10") (pinfunction "~{INTA}_10") (pintype "open_collector+no_connect"))
    )
    (net (code "146") (name "unconnected-(U22-~{INT}B-Pad12)") (class "Default")
      (node (ref "U22") (pin "12") (pinfunction "~{INT}B_12") (pintype "passive+no_connect"))
    )
  )
)
